# probe.net
KiCad netlist of a schematic drawn in EAGLE
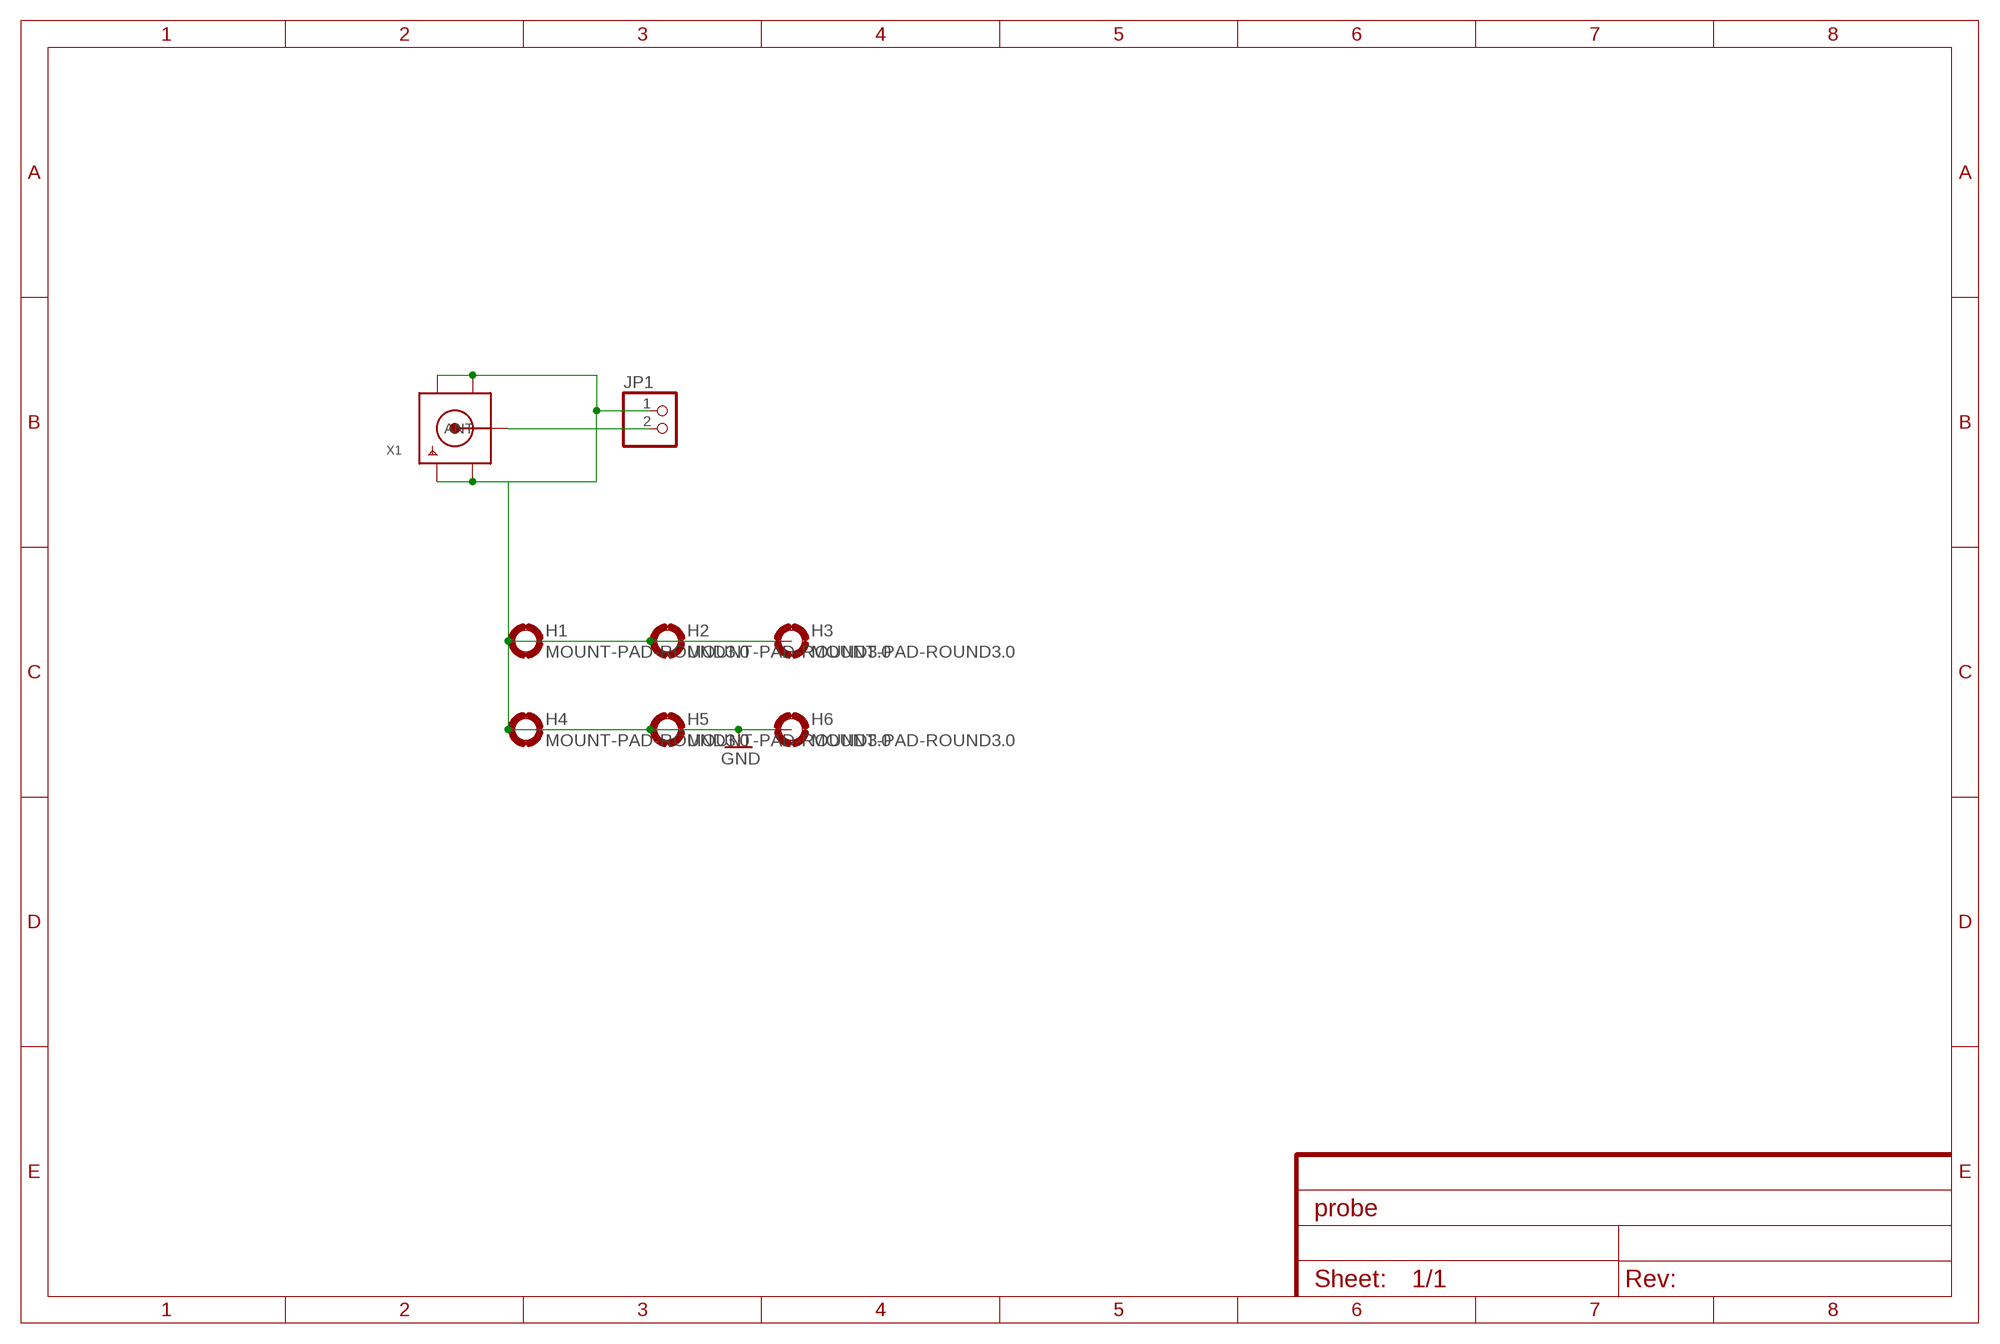
[diagram p0: schematic, sheet 1]

(export (version "E")
  (design (tool "Eeschema 10.0.6"))
  (components
    (comp (ref "H1")
      (value "MOUNT-PAD-ROUND3.0")
      (footprint "eagle-import:3,0-PAD")
      (libsource (lib "eagle-import") (part "MOUNT-PAD-ROUND3.0"))
    )
    (comp (ref "H2")
      (value "MOUNT-PAD-ROUND3.0")
      (footprint "eagle-import:3,0-PAD")
      (libsource (lib "eagle-import") (part "MOUNT-PAD-ROUND3.0"))
    )
    (comp (ref "H3")
      (value "MOUNT-PAD-ROUND3.0")
      (footprint "eagle-import:3,0-PAD")
      (libsource (lib "eagle-import") (part "MOUNT-PAD-ROUND3.0"))
    )
    (comp (ref "H4")
      (value "MOUNT-PAD-ROUND3.0")
      (footprint "eagle-import:3,0-PAD")
      (libsource (lib "eagle-import") (part "MOUNT-PAD-ROUND3.0"))
    )
    (comp (ref "H5")
      (value "MOUNT-PAD-ROUND3.0")
      (footprint "eagle-import:3,0-PAD")
      (libsource (lib "eagle-import") (part "MOUNT-PAD-ROUND3.0"))
    )
    (comp (ref "H6")
      (value "MOUNT-PAD-ROUND3.0")
      (footprint "eagle-import:3,0-PAD")
      (libsource (lib "eagle-import") (part "MOUNT-PAD-ROUND3.0"))
    )
    (comp (ref "JP1")
      (value "TIP-1X2")
      (footprint "eagle-import:TIP-15")
      (libsource (lib "eagle-import") (part "TIP-1X2"))
    )
    (comp (ref "X1")
      (value "SMACONNECTOR_EDGE_UFL")
      (footprint "eagle-import:SMA_EDGELAUNCH_UFL")
      (libsource (lib "eagle-import") (part "SMACONNECTOR_EDGE_UFL"))
    )
  )
  (nets
    (net (code "1") (name "GND") (class "Default")
      (node (ref "H1") (pin "B3,0") (pinfunction "MOUNT_B3,0") (pintype "passive"))
      (node (ref "H2") (pin "B3,0") (pinfunction "MOUNT_B3,0") (pintype "passive"))
      (node (ref "H3") (pin "B3,0") (pinfunction "MOUNT_B3,0") (pintype "passive"))
      (node (ref "H4") (pin "B3,0") (pinfunction "MOUNT_B3,0") (pintype "passive"))
      (node (ref "H5") (pin "B3,0") (pinfunction "MOUNT_B3,0") (pintype "passive"))
      (node (ref "H6") (pin "B3,0") (pinfunction "MOUNT_B3,0") (pintype "passive"))
      (node (ref "JP1") (pin "1") (pinfunction "1_1") (pintype "passive"))
      (node (ref "X1") (pin "GND@1") (pinfunction "GND1_GND@1") (pintype "power_in"))
      (node (ref "X1") (pin "GND@2") (pinfunction "GND2_GND@2") (pintype "power_in"))
      (node (ref "X1") (pin "GND@3") (pinfunction "GND3_GND@3") (pintype "power_in"))
      (node (ref "X1") (pin "GND@4") (pinfunction "GND4_GND@4") (pintype "power_in"))
    )
    (net (code "2") (name "Net-(X1-ANT)") (class "Default")
      (node (ref "JP1") (pin "2") (pinfunction "2_2") (pintype "passive"))
      (node (ref "X1") (pin "P") (pinfunction "ANT_P") (pintype "bidirectional"))
    )
  )
)
